# power.net
KiCad netlist of a schematic drawn in Altium Designer
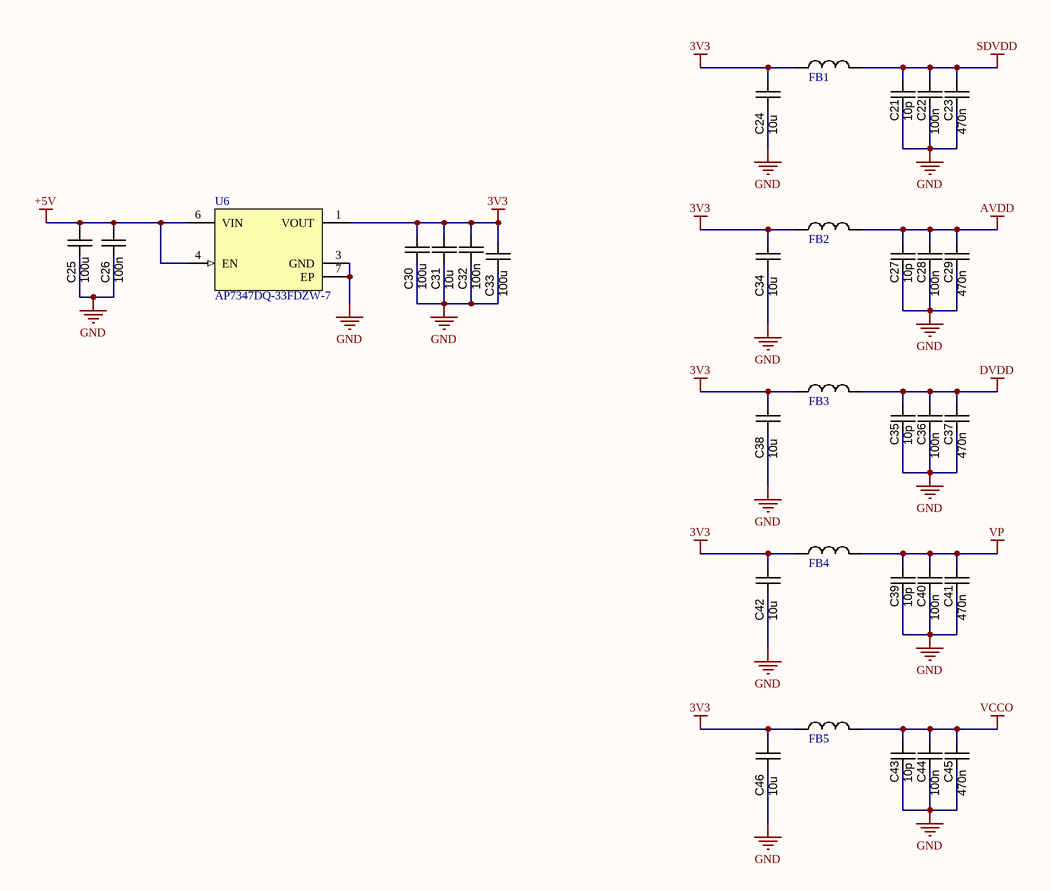
[diagram p0: power.SchDoc]

(export (version "E")
  (design (tool "Eeschema 10.0.6"))
  (components
    (comp (ref "C21")
      (value "10p")
      (footprint "CAPC1005N")
      (description "Capacitor SMD Cer 10nF 10% 16V X7R 0402")
      (fields (field (name "TOLERANCE") "±10%"))
      (libsource (lib "PBL - Capacitors") (part "CAPC_10n_0402_16V_10%"))
    )
    (comp (ref "C22")
      (value "100n")
      (footprint "CAPC1005N")
      (description "Capacitor SMD Cer 10nF 10% 16V X7R 0402")
      (fields (field (name "TOLERANCE") "±10%"))
      (libsource (lib "PBL - Capacitors") (part "CAPC_10n_0402_16V_10%"))
    )
    (comp (ref "C23")
      (value "470n")
      (footprint "CAPC1005N")
      (description "Capacitor SMD Cer 10nF 10% 16V X7R 0402")
      (fields (field (name "TOLERANCE") "±10%"))
      (libsource (lib "PBL - Capacitors") (part "CAPC_10n_0402_16V_10%"))
    )
    (comp (ref "C24")
      (value "10u")
      (footprint "CAPC1608N")
      (description "Capacitor SMD Cer 560pF 5% 50V NP0 0603")
      (fields (field (name "Comment") "approved sub OK"))
      (libsource (lib "PBL - Capacitors") (part "CAPC_560p_0603_5%"))
    )
    (comp (ref "C25")
      (value "100u")
      (footprint "CAPC2012N")
      (description "Capacitor SMD Cer 1uF 10% 16V X7R 0805")
      (fields (field (name "TOLERANCE") "±10%") (field (name "Comment") "approved sub OK"))
      (libsource (lib "PBL - Capacitors") (part "CAPC_1u_0805"))
    )
    (comp (ref "C26")
      (value "100n")
      (footprint "CAPC1005N")
      (description "Capacitor SMD Cer 10nF 10% 16V X7R 0402")
      (fields (field (name "TOLERANCE") "±10%"))
      (libsource (lib "PBL - Capacitors") (part "CAPC_10n_0402_16V_10%"))
    )
    (comp (ref "C27")
      (value "10p")
      (footprint "CAPC1005N")
      (description "Capacitor SMD Cer 10nF 10% 16V X7R 0402")
      (fields (field (name "TOLERANCE") "±10%"))
      (libsource (lib "PBL - Capacitors") (part "CAPC_10n_0402_16V_10%"))
    )
    (comp (ref "C28")
      (value "100n")
      (footprint "CAPC1005N")
      (description "Capacitor SMD Cer 10nF 10% 16V X7R 0402")
      (fields (field (name "TOLERANCE") "±10%"))
      (libsource (lib "PBL - Capacitors") (part "CAPC_10n_0402_16V_10%"))
    )
    (comp (ref "C29")
      (value "470n")
      (footprint "CAPC1005N")
      (description "Capacitor SMD Cer 10nF 10% 16V X7R 0402")
      (fields (field (name "TOLERANCE") "±10%"))
      (libsource (lib "PBL - Capacitors") (part "CAPC_10n_0402_16V_10%"))
    )
    (comp (ref "C30")
      (value "100u")
      (footprint "CAPC2012N")
      (description "Capacitor SMD Cer 1uF 10% 16V X7R 0805")
      (fields (field (name "TOLERANCE") "±10%") (field (name "Comment") "approved sub OK"))
      (libsource (lib "PBL - Capacitors") (part "CAPC_1u_0805"))
    )
    (comp (ref "C31")
      (value "10u")
      (footprint "CAPC1608N")
      (description "Capacitor SMD Cer 560pF 5% 50V NP0 0603")
      (fields (field (name "Comment") "approved sub OK"))
      (libsource (lib "PBL - Capacitors") (part "CAPC_560p_0603_5%"))
    )
    (comp (ref "C32")
      (value "100n")
      (footprint "CAPC1005N")
      (description "Capacitor SMD Cer 10nF 10% 16V X7R 0402")
      (fields (field (name "TOLERANCE") "±10%"))
      (libsource (lib "PBL - Capacitors") (part "CAPC_10n_0402_16V_10%"))
    )
    (comp (ref "C33")
      (value "100u")
      (footprint "CAPC2012N")
      (description "Capacitor SMD Cer 1uF 10% 16V X7R 0805")
      (fields (field (name "TOLERANCE") "±10%") (field (name "Comment") "approved sub OK"))
      (libsource (lib "PBL - Capacitors") (part "CAPC_1u_0805"))
    )
    (comp (ref "C34")
      (value "10u")
      (footprint "CAPC1608N")
      (description "Capacitor SMD Cer 560pF 5% 50V NP0 0603")
      (fields (field (name "Comment") "approved sub OK"))
      (libsource (lib "PBL - Capacitors") (part "CAPC_560p_0603_5%"))
    )
    (comp (ref "C35")
      (value "10p")
      (footprint "CAPC1005N")
      (description "Capacitor SMD Cer 10nF 10% 16V X7R 0402")
      (fields (field (name "TOLERANCE") "±10%"))
      (libsource (lib "PBL - Capacitors") (part "CAPC_10n_0402_16V_10%"))
    )
    (comp (ref "C36")
      (value "100n")
      (footprint "CAPC1005N")
      (description "Capacitor SMD Cer 10nF 10% 16V X7R 0402")
      (fields (field (name "TOLERANCE") "±10%"))
      (libsource (lib "PBL - Capacitors") (part "CAPC_10n_0402_16V_10%"))
    )
    (comp (ref "C37")
      (value "470n")
      (footprint "CAPC1005N")
      (description "Capacitor SMD Cer 10nF 10% 16V X7R 0402")
      (fields (field (name "TOLERANCE") "±10%"))
      (libsource (lib "PBL - Capacitors") (part "CAPC_10n_0402_16V_10%"))
    )
    (comp (ref "C38")
      (value "10u")
      (footprint "CAPC1608N")
      (description "Capacitor SMD Cer 560pF 5% 50V NP0 0603")
      (fields (field (name "Comment") "approved sub OK"))
      (libsource (lib "PBL - Capacitors") (part "CAPC_560p_0603_5%"))
    )
    (comp (ref "C39")
      (value "10p")
      (footprint "CAPC1005N")
      (description "Capacitor SMD Cer 10nF 10% 16V X7R 0402")
      (fields (field (name "TOLERANCE") "±10%"))
      (libsource (lib "PBL - Capacitors") (part "CAPC_10n_0402_16V_10%"))
    )
    (comp (ref "C40")
      (value "100n")
      (footprint "CAPC1005N")
      (description "Capacitor SMD Cer 10nF 10% 16V X7R 0402")
      (fields (field (name "TOLERANCE") "±10%"))
      (libsource (lib "PBL - Capacitors") (part "CAPC_10n_0402_16V_10%"))
    )
    (comp (ref "C41")
      (value "470n")
      (footprint "CAPC1005N")
      (description "Capacitor SMD Cer 10nF 10% 16V X7R 0402")
      (fields (field (name "TOLERANCE") "±10%"))
      (libsource (lib "PBL - Capacitors") (part "CAPC_10n_0402_16V_10%"))
    )
    (comp (ref "C42")
      (value "10u")
      (footprint "CAPC1608N")
      (description "Capacitor SMD Cer 560pF 5% 50V NP0 0603")
      (fields (field (name "Comment") "approved sub OK"))
      (libsource (lib "PBL - Capacitors") (part "CAPC_560p_0603_5%"))
    )
    (comp (ref "C43")
      (value "10p")
      (footprint "CAPC1005N")
      (description "Capacitor SMD Cer 10nF 10% 16V X7R 0402")
      (fields (field (name "TOLERANCE") "±10%"))
      (libsource (lib "PBL - Capacitors") (part "CAPC_10n_0402_16V_10%"))
    )
    (comp (ref "C44")
      (value "100n")
      (footprint "CAPC1005N")
      (description "Capacitor SMD Cer 10nF 10% 16V X7R 0402")
      (fields (field (name "TOLERANCE") "±10%"))
      (libsource (lib "PBL - Capacitors") (part "CAPC_10n_0402_16V_10%"))
    )
    (comp (ref "C45")
      (value "470n")
      (footprint "CAPC1005N")
      (description "Capacitor SMD Cer 10nF 10% 16V X7R 0402")
      (fields (field (name "TOLERANCE") "±10%"))
      (libsource (lib "PBL - Capacitors") (part "CAPC_10n_0402_16V_10%"))
    )
    (comp (ref "C46")
      (value "10u")
      (footprint "CAPC1608N")
      (description "Capacitor SMD Cer 560pF 5% 50V NP0 0603")
      (fields (field (name "Comment") "approved sub OK"))
      (libsource (lib "PBL - Capacitors") (part "CAPC_560p_0603_5%"))
    )
    (comp (ref "FB1") (value "Ferrite") (footprint "INDC1608N") (libsource (lib "cvlib") (part "Ferrite")))
    (comp (ref "FB2") (value "Ferrite") (footprint "INDC1608N") (libsource (lib "cvlib") (part "Ferrite")))
    (comp (ref "FB3") (value "Ferrite") (footprint "INDC1608N") (libsource (lib "cvlib") (part "Ferrite")))
    (comp (ref "FB4") (value "Ferrite") (footprint "INDC1608N") (libsource (lib "cvlib") (part "Ferrite")))
    (comp (ref "FB5") (value "Ferrite") (footprint "INDC1608N") (libsource (lib "cvlib") (part "Ferrite")))
    (comp (ref "U6")
      (value "AP7347DQ-33FDZW-7")
      (footprint "WDFN2020-6")
      (description "Linear Voltage Regulator IC Positive 500mA Very High PSRR")
      (fields (field (name "MF") "Diodes Inc.") (field (name "MP") "AP7361C-FGE-7"))
      (libsource (lib "cvlib") (part "AP7347DQ-33FDZW-7"))
    )
  )
  (nets
    (net (code "1") (name "+5V") (class "Default")
      (node (ref "C25") (pin "1") (pintype "passive"))
      (node (ref "C26") (pin "2") (pintype "passive"))
      (node (ref "U6") (pin "4") (pinfunction "EN_4") (pintype "input"))
      (node (ref "U6") (pin "6") (pinfunction "VIN_6") (pintype "power_in"))
    )
    (net (code "2") (name "3V3") (class "Default")
      (node (ref "C24") (pin "1") (pintype "passive"))
      (node (ref "C30") (pin "1") (pintype "passive"))
      (node (ref "C31") (pin "1") (pintype "passive"))
      (node (ref "C32") (pin "2") (pintype "passive"))
      (node (ref "C33") (pin "1") (pintype "passive"))
      (node (ref "C34") (pin "1") (pintype "passive"))
      (node (ref "C38") (pin "1") (pintype "passive"))
      (node (ref "C42") (pin "1") (pintype "passive"))
      (node (ref "C46") (pin "1") (pintype "passive"))
      (node (ref "FB1") (pin "1") (pinfunction "1_1") (pintype "passive"))
      (node (ref "FB2") (pin "1") (pinfunction "1_1") (pintype "passive"))
      (node (ref "FB3") (pin "1") (pinfunction "1_1") (pintype "passive"))
      (node (ref "FB4") (pin "1") (pinfunction "1_1") (pintype "passive"))
      (node (ref "FB5") (pin "1") (pinfunction "1_1") (pintype "passive"))
      (node (ref "U6") (pin "1") (pinfunction "VOUT_1") (pintype "power_in"))
    )
    (net (code "3") (name "AVDD") (class "Default")
      (node (ref "C27") (pin "1") (pintype "passive"))
      (node (ref "C28") (pin "1") (pintype "passive"))
      (node (ref "C29") (pin "1") (pintype "passive"))
      (node (ref "FB2") (pin "2") (pinfunction "2_2") (pintype "passive"))
    )
    (net (code "4") (name "DVDD") (class "Default")
      (node (ref "C35") (pin "1") (pintype "passive"))
      (node (ref "C36") (pin "1") (pintype "passive"))
      (node (ref "C37") (pin "1") (pintype "passive"))
      (node (ref "FB3") (pin "2") (pinfunction "2_2") (pintype "passive"))
    )
    (net (code "5") (name "GND") (class "Default")
      (node (ref "C21") (pin "2") (pintype "passive"))
      (node (ref "C22") (pin "2") (pintype "passive"))
      (node (ref "C23") (pin "2") (pintype "passive"))
      (node (ref "C24") (pin "2") (pintype "passive"))
      (node (ref "C25") (pin "2") (pintype "passive"))
      (node (ref "C26") (pin "1") (pintype "passive"))
      (node (ref "C27") (pin "2") (pintype "passive"))
      (node (ref "C28") (pin "2") (pintype "passive"))
      (node (ref "C29") (pin "2") (pintype "passive"))
      (node (ref "C30") (pin "2") (pintype "passive"))
      (node (ref "C31") (pin "2") (pintype "passive"))
      (node (ref "C32") (pin "1") (pintype "passive"))
      (node (ref "C33") (pin "2") (pintype "passive"))
      (node (ref "C34") (pin "2") (pintype "passive"))
      (node (ref "C35") (pin "2") (pintype "passive"))
      (node (ref "C36") (pin "2") (pintype "passive"))
      (node (ref "C37") (pin "2") (pintype "passive"))
      (node (ref "C38") (pin "2") (pintype "passive"))
      (node (ref "C39") (pin "2") (pintype "passive"))
      (node (ref "C40") (pin "2") (pintype "passive"))
      (node (ref "C41") (pin "2") (pintype "passive"))
      (node (ref "C42") (pin "2") (pintype "passive"))
      (node (ref "C43") (pin "2") (pintype "passive"))
      (node (ref "C44") (pin "2") (pintype "passive"))
      (node (ref "C45") (pin "2") (pintype "passive"))
      (node (ref "C46") (pin "2") (pintype "passive"))
      (node (ref "U6") (pin "3") (pinfunction "GND_3") (pintype "passive"))
      (node (ref "U6") (pin "7") (pinfunction "EP_7") (pintype "power_in"))
    )
    (net (code "6") (name "SDVDD") (class "Default")
      (node (ref "C21") (pin "1") (pintype "passive"))
      (node (ref "C22") (pin "1") (pintype "passive"))
      (node (ref "C23") (pin "1") (pintype "passive"))
      (node (ref "FB1") (pin "2") (pinfunction "2_2") (pintype "passive"))
    )
    (net (code "7") (name "VCCO") (class "Default")
      (node (ref "C43") (pin "1") (pintype "passive"))
      (node (ref "C44") (pin "1") (pintype "passive"))
      (node (ref "C45") (pin "1") (pintype "passive"))
      (node (ref "FB5") (pin "2") (pinfunction "2_2") (pintype "passive"))
    )
    (net (code "8") (name "VP") (class "Default")
      (node (ref "C39") (pin "1") (pintype "passive"))
      (node (ref "C40") (pin "1") (pintype "passive"))
      (node (ref "C41") (pin "1") (pintype "passive"))
      (node (ref "FB4") (pin "2") (pinfunction "2_2") (pintype "passive"))
    )
  )
)
